# BusCon.net
KiCad netlist of a schematic drawn in EAGLE
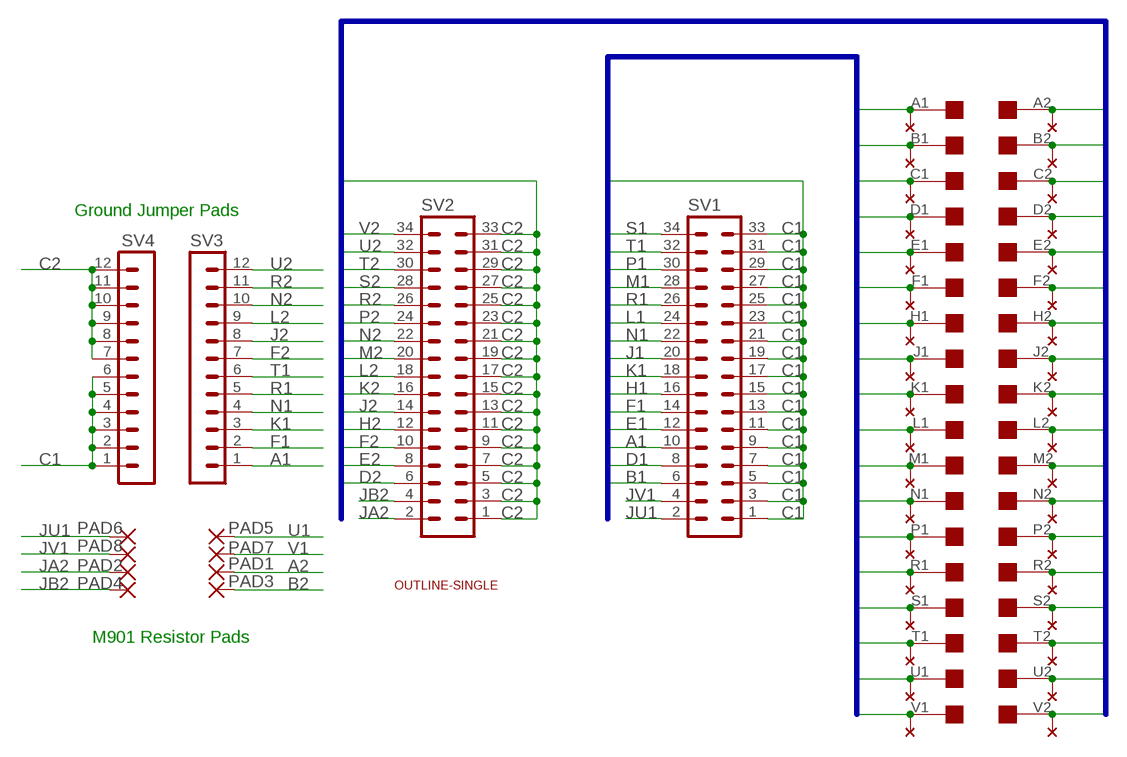
[diagram p0: schematic, sheet 1]

(export (version "E")
  (design (tool "Eeschema 10.0.6"))
  (components
    (comp (ref "PAD1")
      (value "1,6/0,8")
      (footprint "eagle-import:1,6_0,8")
      (libsource (lib "eagle-import") (part "1,6/0,8"))
    )
    (comp (ref "PAD2")
      (value "1,6/0,8")
      (footprint "eagle-import:1,6_0,8")
      (libsource (lib "eagle-import") (part "1,6/0,8"))
    )
    (comp (ref "PAD3")
      (value "1,6/0,8")
      (footprint "eagle-import:1,6_0,8")
      (libsource (lib "eagle-import") (part "1,6/0,8"))
    )
    (comp (ref "PAD4")
      (value "1,6/0,8")
      (footprint "eagle-import:1,6_0,8")
      (libsource (lib "eagle-import") (part "1,6/0,8"))
    )
    (comp (ref "PAD5")
      (value "1,6/0,8")
      (footprint "eagle-import:1,6_0,8")
      (libsource (lib "eagle-import") (part "1,6/0,8"))
    )
    (comp (ref "PAD6")
      (value "1,6/0,8")
      (footprint "eagle-import:1,6_0,8")
      (libsource (lib "eagle-import") (part "1,6/0,8"))
    )
    (comp (ref "PAD7")
      (value "1,6/0,8")
      (footprint "eagle-import:1,6_0,8")
      (libsource (lib "eagle-import") (part "1,6/0,8"))
    )
    (comp (ref "PAD8")
      (value "1,6/0,8")
      (footprint "eagle-import:1,6_0,8")
      (libsource (lib "eagle-import") (part "1,6/0,8"))
    )
    (comp (ref "SV1")
      (value "MA17-2")
      (footprint "eagle-import:MA17-2")
      (libsource (lib "eagle-import") (part "MA17-2"))
    )
    (comp (ref "SV2")
      (value "MA17-2")
      (footprint "eagle-import:MA17-2")
      (libsource (lib "eagle-import") (part "MA17-2"))
    )
    (comp (ref "SV3")
      (value "MA12-1")
      (footprint "eagle-import:MA12-1")
      (libsource (lib "eagle-import") (part "MA12-1"))
    )
    (comp (ref "SV4")
      (value "MA12-1")
      (footprint "eagle-import:MA12-1")
      (libsource (lib "eagle-import") (part "MA12-1"))
    )
    (comp (ref "U$1")
      (value "OUTLINE-SINGLE")
      (footprint "eagle-import:SINGLE")
      (libsource (lib "eagle-import") (part "OUTLINE-SINGLE"))
    )
    (comp (ref "U$4")
      (value "SINGLE")
      (footprint "eagle-import:EDGE-CON2")
      (libsource (lib "eagle-import") (part "SINGLE"))
    )
    (comp (ref "U$5")
      (value "THRU-HOLE2C")
      (footprint "eagle-import:THRU-HOLEC")
      (libsource (lib "eagle-import") (part "THRU-HOLE2C"))
    )
  )
  (nets
    (net (code "1") (name "/A1") (class "Default")
      (node (ref "SV1") (pin "10") (pinfunction "10_10") (pintype "passive"))
      (node (ref "SV3") (pin "1") (pinfunction "1_1") (pintype "passive"))
      (node (ref "U$4") (pin "A1") (pinfunction "1_A1") (pintype "bidirectional"))
      (node (ref "U$5") (pin "A1") (pinfunction "P$1_A1") (pintype "passive"))
    )
    (net (code "2") (name "/A2") (class "Default")
      (node (ref "PAD1") (pin "1") (pinfunction "P_1") (pintype "passive"))
      (node (ref "U$4") (pin "A2") (pinfunction "1_A2") (pintype "bidirectional"))
      (node (ref "U$5") (pin "A2") (pinfunction "P$1_A2") (pintype "passive"))
    )
    (net (code "3") (name "/B1") (class "Default")
      (node (ref "SV1") (pin "6") (pinfunction "6_6") (pintype "passive"))
      (node (ref "U$4") (pin "B1") (pinfunction "1_B1") (pintype "bidirectional"))
      (node (ref "U$5") (pin "B1") (pinfunction "P$1_B1") (pintype "passive"))
    )
    (net (code "4") (name "/B2") (class "Default")
      (node (ref "PAD3") (pin "1") (pinfunction "P_1") (pintype "passive"))
      (node (ref "U$4") (pin "B2") (pinfunction "1_B2") (pintype "bidirectional"))
      (node (ref "U$5") (pin "B2") (pinfunction "P$1_B2") (pintype "passive"))
    )
    (net (code "5") (name "/C1") (class "Default")
      (node (ref "SV1") (pin "1") (pinfunction "1_1") (pintype "passive"))
      (node (ref "SV1") (pin "11") (pinfunction "11_11") (pintype "passive"))
      (node (ref "SV1") (pin "13") (pinfunction "13_13") (pintype "passive"))
      (node (ref "SV1") (pin "15") (pinfunction "15_15") (pintype "passive"))
      (node (ref "SV1") (pin "17") (pinfunction "17_17") (pintype "passive"))
      (node (ref "SV1") (pin "19") (pinfunction "19_19") (pintype "passive"))
      (node (ref "SV1") (pin "21") (pinfunction "21_21") (pintype "passive"))
      (node (ref "SV1") (pin "23") (pinfunction "23_23") (pintype "passive"))
      (node (ref "SV1") (pin "25") (pinfunction "25_25") (pintype "passive"))
      (node (ref "SV1") (pin "27") (pinfunction "27_27") (pintype "passive"))
      (node (ref "SV1") (pin "29") (pinfunction "29_29") (pintype "passive"))
      (node (ref "SV1") (pin "3") (pinfunction "3_3") (pintype "passive"))
      (node (ref "SV1") (pin "31") (pinfunction "31_31") (pintype "passive"))
      (node (ref "SV1") (pin "33") (pinfunction "33_33") (pintype "passive"))
      (node (ref "SV1") (pin "5") (pinfunction "5_5") (pintype "passive"))
      (node (ref "SV1") (pin "7") (pinfunction "7_7") (pintype "passive"))
      (node (ref "SV1") (pin "9") (pinfunction "9_9") (pintype "passive"))
      (node (ref "SV4") (pin "1") (pinfunction "1_1") (pintype "passive"))
      (node (ref "SV4") (pin "2") (pinfunction "2_2") (pintype "passive"))
      (node (ref "SV4") (pin "3") (pinfunction "3_3") (pintype "passive"))
      (node (ref "SV4") (pin "4") (pinfunction "4_4") (pintype "passive"))
      (node (ref "SV4") (pin "5") (pinfunction "5_5") (pintype "passive"))
      (node (ref "SV4") (pin "6") (pinfunction "6_6") (pintype "passive"))
      (node (ref "U$4") (pin "C1") (pinfunction "1_C1") (pintype "bidirectional"))
      (node (ref "U$5") (pin "C1") (pinfunction "P$1_C1") (pintype "passive"))
    )
    (net (code "6") (name "/C2") (class "Default")
      (node (ref "SV2") (pin "1") (pinfunction "1_1") (pintype "passive"))
      (node (ref "SV2") (pin "11") (pinfunction "11_11") (pintype "passive"))
      (node (ref "SV2") (pin "13") (pinfunction "13_13") (pintype "passive"))
      (node (ref "SV2") (pin "15") (pinfunction "15_15") (pintype "passive"))
      (node (ref "SV2") (pin "17") (pinfunction "17_17") (pintype "passive"))
      (node (ref "SV2") (pin "19") (pinfunction "19_19") (pintype "passive"))
      (node (ref "SV2") (pin "21") (pinfunction "21_21") (pintype "passive"))
      (node (ref "SV2") (pin "23") (pinfunction "23_23") (pintype "passive"))
      (node (ref "SV2") (pin "25") (pinfunction "25_25") (pintype "passive"))
      (node (ref "SV2") (pin "27") (pinfunction "27_27") (pintype "passive"))
      (node (ref "SV2") (pin "29") (pinfunction "29_29") (pintype "passive"))
      (node (ref "SV2") (pin "3") (pinfunction "3_3") (pintype "passive"))
      (node (ref "SV2") (pin "31") (pinfunction "31_31") (pintype "passive"))
      (node (ref "SV2") (pin "33") (pinfunction "33_33") (pintype "passive"))
      (node (ref "SV2") (pin "5") (pinfunction "5_5") (pintype "passive"))
      (node (ref "SV2") (pin "7") (pinfunction "7_7") (pintype "passive"))
      (node (ref "SV2") (pin "9") (pinfunction "9_9") (pintype "passive"))
      (node (ref "SV4") (pin "10") (pinfunction "10_10") (pintype "passive"))
      (node (ref "SV4") (pin "11") (pinfunction "11_11") (pintype "passive"))
      (node (ref "SV4") (pin "12") (pinfunction "12_12") (pintype "passive"))
      (node (ref "SV4") (pin "7") (pinfunction "7_7") (pintype "passive"))
      (node (ref "SV4") (pin "8") (pinfunction "8_8") (pintype "passive"))
      (node (ref "SV4") (pin "9") (pinfunction "9_9") (pintype "passive"))
      (node (ref "U$4") (pin "C2") (pinfunction "1_C2") (pintype "bidirectional"))
      (node (ref "U$5") (pin "C2") (pinfunction "P$1_C2") (pintype "passive"))
    )
    (net (code "7") (name "/D1") (class "Default")
      (node (ref "SV1") (pin "8") (pinfunction "8_8") (pintype "passive"))
      (node (ref "U$4") (pin "D1") (pinfunction "1_D1") (pintype "bidirectional"))
      (node (ref "U$5") (pin "D1") (pinfunction "P$1_D1") (pintype "passive"))
    )
    (net (code "8") (name "/D2") (class "Default")
      (node (ref "SV2") (pin "6") (pinfunction "6_6") (pintype "passive"))
      (node (ref "U$4") (pin "D2") (pinfunction "1_D2") (pintype "bidirectional"))
      (node (ref "U$5") (pin "D2") (pinfunction "P$1_D2") (pintype "passive"))
    )
    (net (code "9") (name "/E1") (class "Default")
      (node (ref "SV1") (pin "12") (pinfunction "12_12") (pintype "passive"))
      (node (ref "U$4") (pin "E1") (pinfunction "1_E1") (pintype "bidirectional"))
      (node (ref "U$5") (pin "E1") (pinfunction "P$1_E1") (pintype "passive"))
    )
    (net (code "10") (name "/E2") (class "Default")
      (node (ref "SV2") (pin "8") (pinfunction "8_8") (pintype "passive"))
      (node (ref "U$4") (pin "E2") (pinfunction "1_E2") (pintype "bidirectional"))
      (node (ref "U$5") (pin "E2") (pinfunction "P$1_E2") (pintype "passive"))
    )
    (net (code "11") (name "/F1") (class "Default")
      (node (ref "SV1") (pin "14") (pinfunction "14_14") (pintype "passive"))
      (node (ref "SV3") (pin "2") (pinfunction "2_2") (pintype "passive"))
      (node (ref "U$4") (pin "F1") (pinfunction "1_F1") (pintype "bidirectional"))
      (node (ref "U$5") (pin "F1") (pinfunction "P$1_F1") (pintype "passive"))
    )
    (net (code "12") (name "/F2") (class "Default")
      (node (ref "SV2") (pin "10") (pinfunction "10_10") (pintype "passive"))
      (node (ref "SV3") (pin "7") (pinfunction "7_7") (pintype "passive"))
      (node (ref "U$4") (pin "F2") (pinfunction "1_F2") (pintype "bidirectional"))
      (node (ref "U$5") (pin "F2") (pinfunction "P$1_F2") (pintype "passive"))
    )
    (net (code "13") (name "/H1") (class "Default")
      (node (ref "SV1") (pin "16") (pinfunction "16_16") (pintype "passive"))
      (node (ref "U$4") (pin "H1") (pinfunction "1_H1") (pintype "bidirectional"))
      (node (ref "U$5") (pin "H1") (pinfunction "P$1_H1") (pintype "passive"))
    )
    (net (code "14") (name "/H2") (class "Default")
      (node (ref "SV2") (pin "12") (pinfunction "12_12") (pintype "passive"))
      (node (ref "U$4") (pin "H2") (pinfunction "1_H2") (pintype "bidirectional"))
      (node (ref "U$5") (pin "H2") (pinfunction "P$1_H2") (pintype "passive"))
    )
    (net (code "15") (name "/J1") (class "Default")
      (node (ref "SV1") (pin "20") (pinfunction "20_20") (pintype "passive"))
      (node (ref "U$4") (pin "J1") (pinfunction "1_J1") (pintype "bidirectional"))
      (node (ref "U$5") (pin "J1") (pinfunction "P$1_J1") (pintype "passive"))
    )
    (net (code "16") (name "/J2") (class "Default")
      (node (ref "SV2") (pin "14") (pinfunction "14_14") (pintype "passive"))
      (node (ref "SV3") (pin "8") (pinfunction "8_8") (pintype "passive"))
      (node (ref "U$4") (pin "J2") (pinfunction "1_J2") (pintype "bidirectional"))
      (node (ref "U$5") (pin "J2") (pinfunction "P$1_J2") (pintype "passive"))
    )
    (net (code "17") (name "/JA2") (class "Default")
      (node (ref "PAD2") (pin "1") (pinfunction "P_1") (pintype "passive"))
      (node (ref "SV2") (pin "2") (pinfunction "2_2") (pintype "passive"))
    )
    (net (code "18") (name "/JB2") (class "Default")
      (node (ref "PAD4") (pin "1") (pinfunction "P_1") (pintype "passive"))
      (node (ref "SV2") (pin "4") (pinfunction "4_4") (pintype "passive"))
    )
    (net (code "19") (name "/JU1") (class "Default")
      (node (ref "PAD6") (pin "1") (pinfunction "P_1") (pintype "passive"))
      (node (ref "SV1") (pin "2") (pinfunction "2_2") (pintype "passive"))
    )
    (net (code "20") (name "/JV1") (class "Default")
      (node (ref "PAD8") (pin "1") (pinfunction "P_1") (pintype "passive"))
      (node (ref "SV1") (pin "4") (pinfunction "4_4") (pintype "passive"))
    )
    (net (code "21") (name "/K1") (class "Default")
      (node (ref "SV1") (pin "18") (pinfunction "18_18") (pintype "passive"))
      (node (ref "SV3") (pin "3") (pinfunction "3_3") (pintype "passive"))
      (node (ref "U$4") (pin "K1") (pinfunction "1_K1") (pintype "bidirectional"))
      (node (ref "U$5") (pin "K1") (pinfunction "P$1_K1") (pintype "passive"))
    )
    (net (code "22") (name "/K2") (class "Default")
      (node (ref "SV2") (pin "16") (pinfunction "16_16") (pintype "passive"))
      (node (ref "U$4") (pin "K2") (pinfunction "1_K2") (pintype "bidirectional"))
      (node (ref "U$5") (pin "K2") (pinfunction "P$1_K2") (pintype "passive"))
    )
    (net (code "23") (name "/L1") (class "Default")
      (node (ref "SV1") (pin "24") (pinfunction "24_24") (pintype "passive"))
      (node (ref "U$4") (pin "L1") (pinfunction "1_L1") (pintype "bidirectional"))
      (node (ref "U$5") (pin "L1") (pinfunction "P$1_L1") (pintype "passive"))
    )
    (net (code "24") (name "/L2") (class "Default")
      (node (ref "SV2") (pin "18") (pinfunction "18_18") (pintype "passive"))
      (node (ref "SV3") (pin "9") (pinfunction "9_9") (pintype "passive"))
      (node (ref "U$4") (pin "L2") (pinfunction "1_L2") (pintype "bidirectional"))
      (node (ref "U$5") (pin "L2") (pinfunction "P$1_L2") (pintype "passive"))
    )
    (net (code "25") (name "/M1") (class "Default")
      (node (ref "SV1") (pin "28") (pinfunction "28_28") (pintype "passive"))
      (node (ref "U$4") (pin "M1") (pinfunction "1_M1") (pintype "bidirectional"))
      (node (ref "U$5") (pin "M1") (pinfunction "P$1_M1") (pintype "passive"))
    )
    (net (code "26") (name "/M2") (class "Default")
      (node (ref "SV2") (pin "20") (pinfunction "20_20") (pintype "passive"))
      (node (ref "U$4") (pin "M2") (pinfunction "1_M2") (pintype "bidirectional"))
      (node (ref "U$5") (pin "M2") (pinfunction "P$1_M2") (pintype "passive"))
    )
    (net (code "27") (name "/N1") (class "Default")
      (node (ref "SV1") (pin "22") (pinfunction "22_22") (pintype "passive"))
      (node (ref "SV3") (pin "4") (pinfunction "4_4") (pintype "passive"))
      (node (ref "U$4") (pin "N1") (pinfunction "1_N1") (pintype "bidirectional"))
      (node (ref "U$5") (pin "N1") (pinfunction "P$1_N1") (pintype "passive"))
    )
    (net (code "28") (name "/N2") (class "Default")
      (node (ref "SV2") (pin "22") (pinfunction "22_22") (pintype "passive"))
      (node (ref "SV3") (pin "10") (pinfunction "10_10") (pintype "passive"))
      (node (ref "U$4") (pin "N2") (pinfunction "1_N2") (pintype "bidirectional"))
      (node (ref "U$5") (pin "N2") (pinfunction "P$1_N2") (pintype "passive"))
    )
    (net (code "29") (name "/P1") (class "Default")
      (node (ref "SV1") (pin "30") (pinfunction "30_30") (pintype "passive"))
      (node (ref "U$4") (pin "P1") (pinfunction "1_P1") (pintype "bidirectional"))
      (node (ref "U$5") (pin "P1") (pinfunction "P$1_P1") (pintype "passive"))
    )
    (net (code "30") (name "/P2") (class "Default")
      (node (ref "SV2") (pin "24") (pinfunction "24_24") (pintype "passive"))
      (node (ref "U$4") (pin "P2") (pinfunction "1_P2") (pintype "bidirectional"))
      (node (ref "U$5") (pin "P2") (pinfunction "P$1_P2") (pintype "passive"))
    )
    (net (code "31") (name "/R1") (class "Default")
      (node (ref "SV1") (pin "26") (pinfunction "26_26") (pintype "passive"))
      (node (ref "SV3") (pin "5") (pinfunction "5_5") (pintype "passive"))
      (node (ref "U$4") (pin "R1") (pinfunction "1_R1") (pintype "bidirectional"))
      (node (ref "U$5") (pin "R1") (pinfunction "P$1_R1") (pintype "passive"))
    )
    (net (code "32") (name "/R2") (class "Default")
      (node (ref "SV2") (pin "26") (pinfunction "26_26") (pintype "passive"))
      (node (ref "SV3") (pin "11") (pinfunction "11_11") (pintype "passive"))
      (node (ref "U$4") (pin "R2") (pinfunction "1_R2") (pintype "bidirectional"))
      (node (ref "U$5") (pin "R2") (pinfunction "P$1_R2") (pintype "passive"))
    )
    (net (code "33") (name "/S1") (class "Default")
      (node (ref "SV1") (pin "34") (pinfunction "34_34") (pintype "passive"))
      (node (ref "U$4") (pin "S1") (pinfunction "1_S1") (pintype "bidirectional"))
      (node (ref "U$5") (pin "S1") (pinfunction "P$1_S1") (pintype "passive"))
    )
    (net (code "34") (name "/S2") (class "Default")
      (node (ref "SV2") (pin "28") (pinfunction "28_28") (pintype "passive"))
      (node (ref "U$4") (pin "S2") (pinfunction "1_S2") (pintype "bidirectional"))
      (node (ref "U$5") (pin "S2") (pinfunction "P$1_S2") (pintype "passive"))
    )
    (net (code "35") (name "/T1") (class "Default")
      (node (ref "SV1") (pin "32") (pinfunction "32_32") (pintype "passive"))
      (node (ref "SV3") (pin "6") (pinfunction "6_6") (pintype "passive"))
      (node (ref "U$4") (pin "T1") (pinfunction "1_T1") (pintype "bidirectional"))
      (node (ref "U$5") (pin "T1") (pinfunction "P$1_T1") (pintype "passive"))
    )
    (net (code "36") (name "/T2") (class "Default")
      (node (ref "SV2") (pin "30") (pinfunction "30_30") (pintype "passive"))
      (node (ref "U$4") (pin "T2") (pinfunction "1_T2") (pintype "bidirectional"))
      (node (ref "U$5") (pin "T2") (pinfunction "P$1_T2") (pintype "passive"))
    )
    (net (code "37") (name "/U1") (class "Default")
      (node (ref "PAD5") (pin "1") (pinfunction "P_1") (pintype "passive"))
      (node (ref "U$4") (pin "U1") (pinfunction "1_U1") (pintype "bidirectional"))
      (node (ref "U$5") (pin "U1") (pinfunction "P$1_U1") (pintype "passive"))
    )
    (net (code "38") (name "/U2") (class "Default")
      (node (ref "SV2") (pin "32") (pinfunction "32_32") (pintype "passive"))
      (node (ref "SV3") (pin "12") (pinfunction "12_12") (pintype "passive"))
      (node (ref "U$4") (pin "U2") (pinfunction "1_U2") (pintype "bidirectional"))
      (node (ref "U$5") (pin "U2") (pinfunction "P$1_U2") (pintype "passive"))
    )
    (net (code "39") (name "/V1") (class "Default")
      (node (ref "PAD7") (pin "1") (pinfunction "P_1") (pintype "passive"))
      (node (ref "U$4") (pin "V1") (pinfunction "1_V1") (pintype "bidirectional"))
      (node (ref "U$5") (pin "V1") (pinfunction "P$1_V1") (pintype "passive"))
    )
    (net (code "40") (name "/V2") (class "Default")
      (node (ref "SV2") (pin "34") (pinfunction "34_34") (pintype "passive"))
      (node (ref "U$4") (pin "V2") (pinfunction "1_V2") (pintype "bidirectional"))
      (node (ref "U$5") (pin "V2") (pinfunction "P$1_V2") (pintype "passive"))
    )
  )
)
